# Universal_Bicore_rev_A.net
KiCad netlist of a schematic drawn in EAGLE
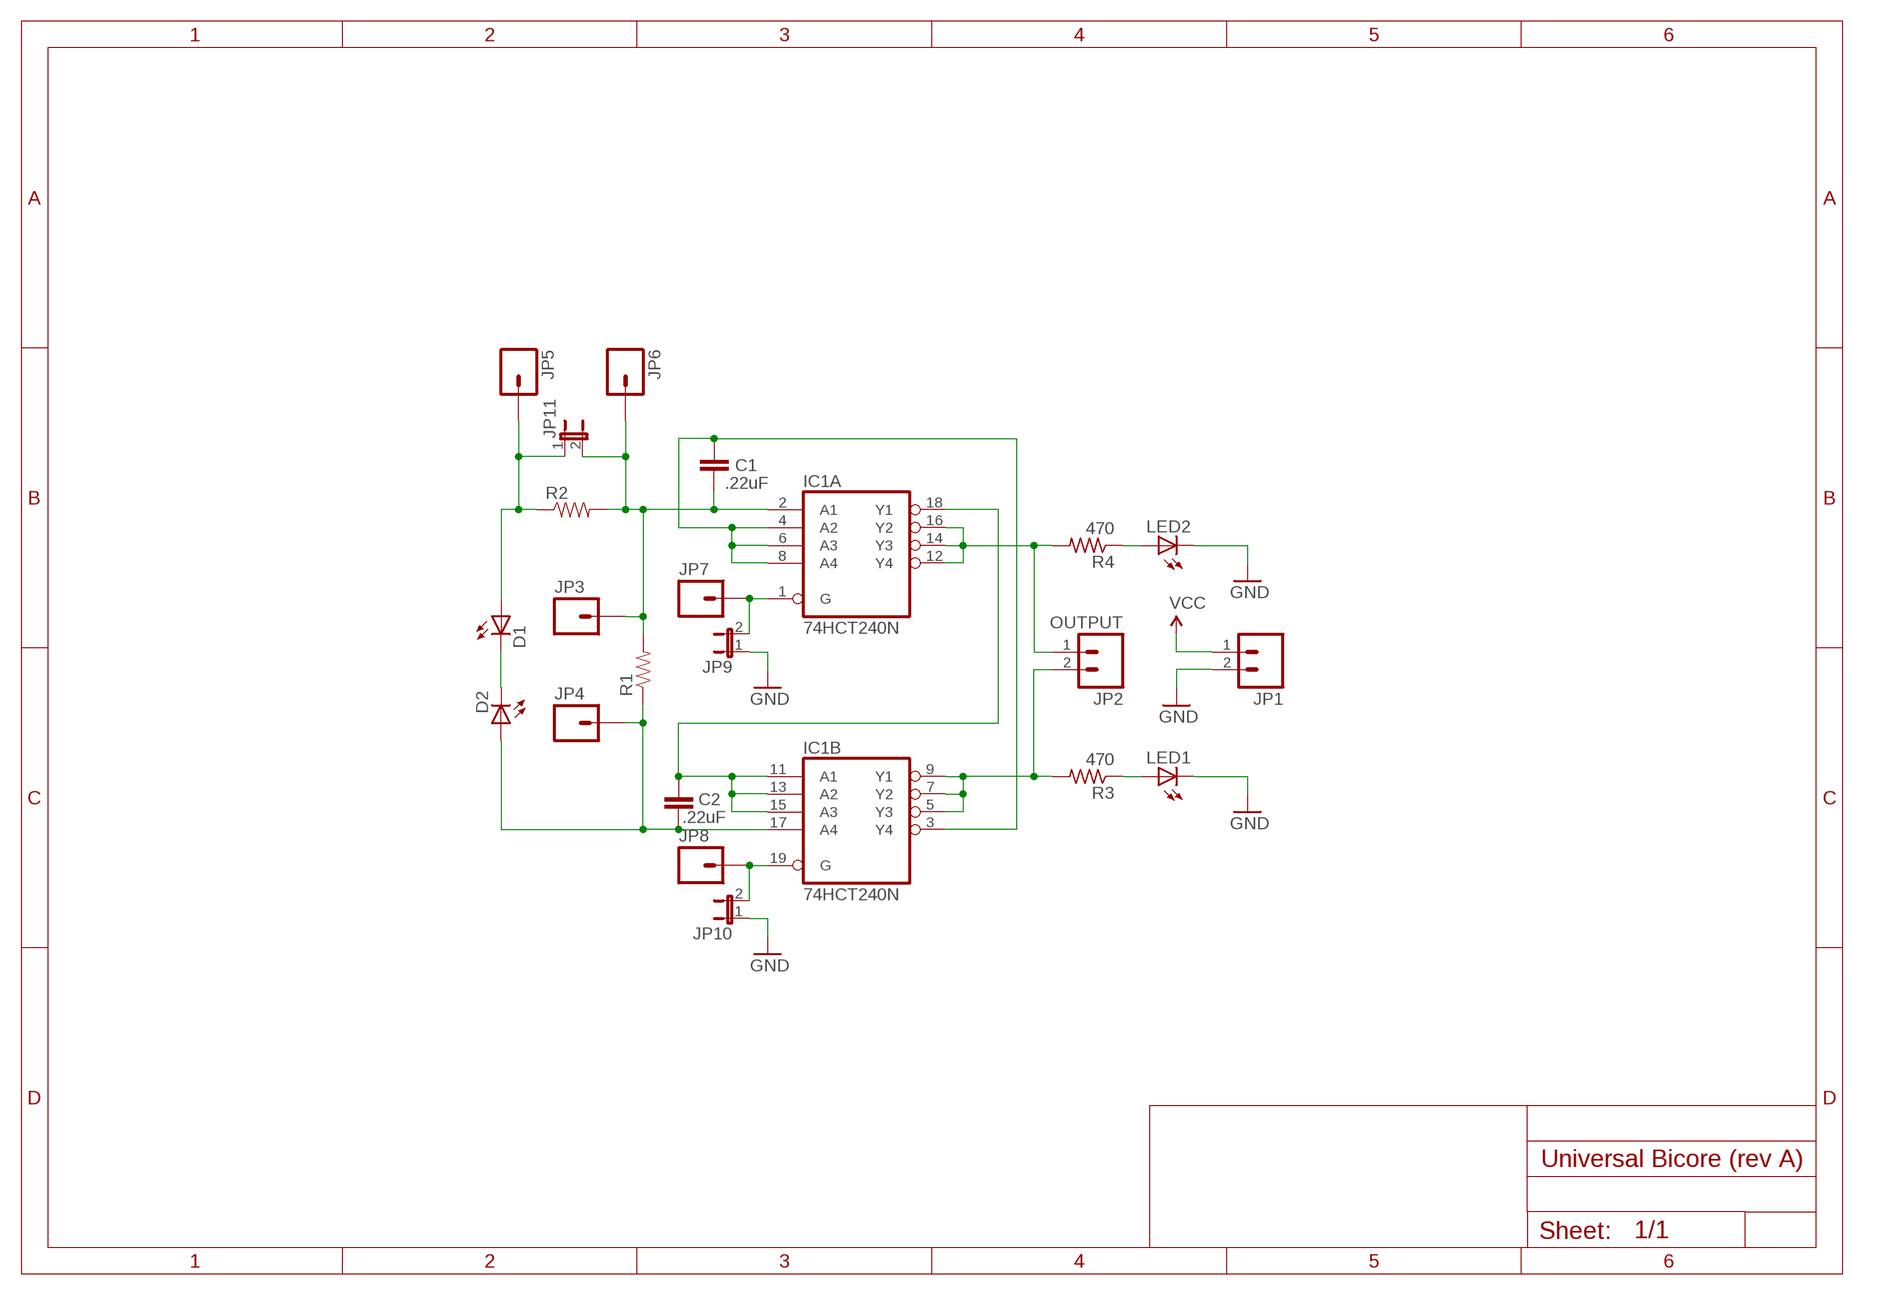
[diagram p0: schematic, sheet 1]

(export (version "E")
  (design (tool "Eeschema 10.0.6"))
  (components
    (comp (ref "C1")
      (value ".22uF")
      (footprint "eagle-import:CAP-PTH-SMALLEZ")
      (libsource (lib "eagle-import") (part "CAPEZ"))
    )
    (comp (ref "C2")
      (value ".22uF")
      (footprint "eagle-import:CAP-PTH-SMALLEZ")
      (libsource (lib "eagle-import") (part "CAPEZ"))
    )
    (comp (ref "D1")
      (value "LED3MM")
      (footprint "eagle-import:LED3MM")
      (libsource (lib "eagle-import") (part "LED3MM"))
    )
    (comp (ref "D2")
      (value "LED3MM")
      (footprint "eagle-import:LED3MM")
      (libsource (lib "eagle-import") (part "LED3MM"))
    )
    (comp (ref "IC1")
      (value "74HCT240N")
      (footprint "eagle-import:DIL20")
      (libsource (lib "eagle-import") (part "74240NHCT"))
    )
    (comp (ref "JP1")
      (value "M02PTH")
      (footprint "eagle-import:1X02")
      (libsource (lib "eagle-import") (part "M02PTH"))
    )
    (comp (ref "JP2")
      (value "OUTPUT")
      (footprint "eagle-import:1X02")
      (libsource (lib "eagle-import") (part "M02PTH"))
    )
    (comp (ref "JP3")
      (value "M01PTH")
      (footprint "eagle-import:1X01")
      (libsource (lib "eagle-import") (part "M01PTH"))
    )
    (comp (ref "JP4")
      (value "M01PTH")
      (footprint "eagle-import:1X01")
      (libsource (lib "eagle-import") (part "M01PTH"))
    )
    (comp (ref "JP5")
      (value "M01PTH")
      (footprint "eagle-import:1X01")
      (libsource (lib "eagle-import") (part "M01PTH"))
    )
    (comp (ref "JP6")
      (value "M01PTH")
      (footprint "eagle-import:1X01")
      (libsource (lib "eagle-import") (part "M01PTH"))
    )
    (comp (ref "JP7")
      (value "M01PTH")
      (footprint "eagle-import:1X01")
      (libsource (lib "eagle-import") (part "M01PTH"))
    )
    (comp (ref "JP8")
      (value "M01PTH")
      (footprint "eagle-import:1X01")
      (libsource (lib "eagle-import") (part "M01PTH"))
    )
    (comp (ref "JP9")
      (value "JUMPER-2SMD-NC")
      (footprint "eagle-import:SJ_2S")
      (libsource (lib "eagle-import") (part "JUMPER-2SMD-NC"))
    )
    (comp (ref "JP10")
      (value "JUMPER-2SMD-NC")
      (footprint "eagle-import:SJ_2S")
      (libsource (lib "eagle-import") (part "JUMPER-2SMD-NC"))
    )
    (comp (ref "JP11")
      (value "JUMPER-2SMD-NC")
      (footprint "eagle-import:SJ_2S")
      (libsource (lib "eagle-import") (part "JUMPER-2SMD-NC"))
    )
    (comp (ref "LED1")
      (value "LEDCHIPLED_0805")
      (footprint "eagle-import:CHIPLED_0805")
      (libsource (lib "eagle-import") (part "LEDCHIPLED_0805"))
    )
    (comp (ref "LED2")
      (value "LEDCHIPLED_0805")
      (footprint "eagle-import:CHIPLED_0805")
      (libsource (lib "eagle-import") (part "LEDCHIPLED_0805"))
    )
    (comp (ref "R1")
      (value "RESISTOREZ")
      (footprint "eagle-import:AXIAL-0.3EZ")
      (libsource (lib "eagle-import") (part "RESISTOREZ"))
    )
    (comp (ref "R2")
      (value "RESISTOREZ")
      (footprint "eagle-import:AXIAL-0.3EZ")
      (libsource (lib "eagle-import") (part "RESISTOREZ"))
    )
    (comp (ref "R3")
      (value "470")
      (footprint "eagle-import:R0805")
      (libsource (lib "eagle-import") (part "R-US_R0805"))
    )
    (comp (ref "R4")
      (value "470")
      (footprint "eagle-import:R0805")
      (libsource (lib "eagle-import") (part "R-US_R0805"))
    )
  )
  (nets
    (net (code "1") (name "GND") (class "Default")
      (node (ref "JP1") (pin "2") (pinfunction "2_2") (pintype "passive"))
      (node (ref "JP10") (pin "1") (pinfunction "1_1") (pintype "passive"))
      (node (ref "JP9") (pin "1") (pinfunction "1_1") (pintype "passive"))
      (node (ref "LED1") (pin "C") (pinfunction "C_C") (pintype "passive"))
      (node (ref "LED2") (pin "C") (pinfunction "C_C") (pintype "passive"))
    )
    (net (code "2") (name "Net-(D1-C)") (class "Default")
      (node (ref "D1") (pin "K") (pinfunction "C_K") (pintype "passive"))
      (node (ref "D2") (pin "K") (pinfunction "C_K") (pintype "passive"))
    )
    (net (code "3") (name "Net-(IC1A-A1)") (class "Default")
      (node (ref "C1") (pin "1") (pinfunction "1_1") (pintype "passive"))
      (node (ref "IC1") (pin "2") (pinfunction "A1_2") (pintype "input"))
      (node (ref "JP11") (pin "2") (pinfunction "2_2") (pintype "passive"))
      (node (ref "JP3") (pin "1") (pinfunction "1_1") (pintype "passive"))
      (node (ref "JP6") (pin "1") (pinfunction "1_1") (pintype "passive"))
      (node (ref "R1") (pin "P$2") (pinfunction "2_P$2") (pintype "passive"))
      (node (ref "R2") (pin "P$2") (pinfunction "2_P$2") (pintype "passive"))
    )
    (net (code "4") (name "Net-(IC1A-A2)") (class "Default")
      (node (ref "C1") (pin "2") (pinfunction "2_2") (pintype "passive"))
      (node (ref "IC1") (pin "3") (pinfunction "Y4_3") (pintype "tri_state"))
      (node (ref "IC1") (pin "4") (pinfunction "A2_4") (pintype "input"))
      (node (ref "IC1") (pin "6") (pinfunction "A3_6") (pintype "input"))
      (node (ref "IC1") (pin "8") (pinfunction "A4_8") (pintype "input"))
    )
    (net (code "5") (name "Net-(IC1A-G)") (class "Default")
      (node (ref "IC1") (pin "1") (pinfunction "G_1") (pintype "input"))
      (node (ref "JP7") (pin "1") (pinfunction "1_1") (pintype "passive"))
      (node (ref "JP9") (pin "2") (pinfunction "2_2") (pintype "passive"))
    )
    (net (code "6") (name "Net-(IC1A-Y1)") (class "Default")
      (node (ref "C2") (pin "1") (pinfunction "1_1") (pintype "passive"))
      (node (ref "IC1") (pin "11") (pinfunction "A1_11") (pintype "input"))
      (node (ref "IC1") (pin "13") (pinfunction "A2_13") (pintype "input"))
      (node (ref "IC1") (pin "15") (pinfunction "A3_15") (pintype "input"))
      (node (ref "IC1") (pin "18") (pinfunction "Y1_18") (pintype "tri_state"))
    )
    (net (code "7") (name "Net-(IC1A-Y2)") (class "Default")
      (node (ref "IC1") (pin "12") (pinfunction "Y4_12") (pintype "tri_state"))
      (node (ref "IC1") (pin "14") (pinfunction "Y3_14") (pintype "tri_state"))
      (node (ref "IC1") (pin "16") (pinfunction "Y2_16") (pintype "tri_state"))
      (node (ref "JP2") (pin "1") (pinfunction "1_1") (pintype "passive"))
      (node (ref "R4") (pin "2") (pinfunction "2_2") (pintype "passive"))
    )
    (net (code "8") (name "Net-(IC1B-A4)") (class "Default")
      (node (ref "C2") (pin "2") (pinfunction "2_2") (pintype "passive"))
      (node (ref "D2") (pin "A") (pinfunction "A_A") (pintype "passive"))
      (node (ref "IC1") (pin "17") (pinfunction "A4_17") (pintype "input"))
      (node (ref "JP4") (pin "1") (pinfunction "1_1") (pintype "passive"))
      (node (ref "R1") (pin "P$1") (pinfunction "1_P$1") (pintype "passive"))
    )
    (net (code "9") (name "Net-(IC1B-G)") (class "Default")
      (node (ref "IC1") (pin "19") (pinfunction "G_19") (pintype "input"))
      (node (ref "JP10") (pin "2") (pinfunction "2_2") (pintype "passive"))
      (node (ref "JP8") (pin "1") (pinfunction "1_1") (pintype "passive"))
    )
    (net (code "10") (name "Net-(IC1B-Y1)") (class "Default")
      (node (ref "IC1") (pin "5") (pinfunction "Y3_5") (pintype "tri_state"))
      (node (ref "IC1") (pin "7") (pinfunction "Y2_7") (pintype "tri_state"))
      (node (ref "IC1") (pin "9") (pinfunction "Y1_9") (pintype "tri_state"))
      (node (ref "JP2") (pin "2") (pinfunction "2_2") (pintype "passive"))
      (node (ref "R3") (pin "2") (pinfunction "2_2") (pintype "passive"))
    )
    (net (code "11") (name "Net-(LED1-PadA)") (class "Default")
      (node (ref "LED1") (pin "A") (pinfunction "A_A") (pintype "passive"))
      (node (ref "R3") (pin "1") (pinfunction "1_1") (pintype "passive"))
    )
    (net (code "12") (name "Net-(LED2-PadA)") (class "Default")
      (node (ref "LED2") (pin "A") (pinfunction "A_A") (pintype "passive"))
      (node (ref "R4") (pin "1") (pinfunction "1_1") (pintype "passive"))
    )
    (net (code "13") (name "Net-(R2-1)") (class "Default")
      (node (ref "D1") (pin "A") (pinfunction "A_A") (pintype "passive"))
      (node (ref "JP11") (pin "1") (pinfunction "1_1") (pintype "passive"))
      (node (ref "JP5") (pin "1") (pinfunction "1_1") (pintype "passive"))
      (node (ref "R2") (pin "P$1") (pinfunction "1_P$1") (pintype "passive"))
    )
    (net (code "14") (name "VCC") (class "Default")
      (node (ref "JP1") (pin "1") (pinfunction "1_1") (pintype "passive"))
    )
  )
)
